# Sheet6_MCU_Antenna_Radio_Interface.net
KiCad netlist of a schematic drawn in Altium Designer
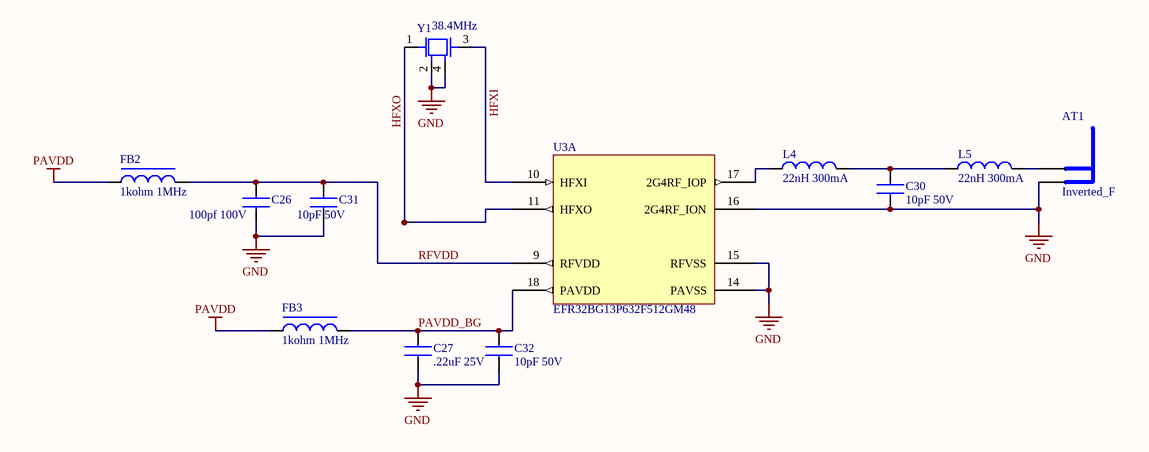
[diagram p0: Sheet6_MCU_Antenna_Radio_Interface.SchDoc]

(export (version "E")
  (design (tool "Eeschema 10.0.6"))
  (components
    (comp (ref "AT1")
      (value "Inverted_F")
      (footprint "F_ANTENNA")
      (description "Inverted-F Antenna for .062\" FR4")
      (libsource (lib "Schlib1 (1)") (part "INVERTED-F_ANTENNA"))
    )
    (comp (ref "C26")
      (value "100pf 100V")
      (footprint "CAP_0805_1_4MM")
      (description "Capacitor 100 pF 100 VDC PU=4000 ST, CL21C101JCANNNC, Samsung")
      (fields
        (field (name "MANUFACTURER") "Samsung")
        (field (name "MANUFACTURER PART NUMBER") "CL21C101JCANNNC")
      )
      (libsource (lib "LPEDT_Parts") (part "CL21C101JCANNNC"))
    )
    (comp (ref "C27")
      (value ".22uF 25V")
      (footprint "CAP_0603_1MM")
      (fields
        (field (name "MANUFACTURER") "Taiyo Yuden")
        (field (name "MANUFACTURER PART NUMBER") "TMK107B7224KA-T")
        (field (name "TOLERANCE") "10%")
      )
      (libsource (lib "LPEDT_Parts") (part "TMK107B7224KA-T"))
    )
    (comp (ref "C30")
      (value "10pF 50V")
      (footprint "CAPC1005X06N")
      (description "Cap Ceramic 10pF 50V X7R 10% SMD 0402 125°C Paper T/R")
      (fields
        (field (name "MANUFACTURER") "KEMET")
        (field (name "MANUFACTURER PART NUMBER") "C0402C100K5RAC7867")
      )
      (libsource (lib "LPEDT_Parts") (part "C0402C100K5RAC7867"))
    )
    (comp (ref "C31")
      (value "10pF 50V")
      (footprint "CAP_0805_1_4MM")
      (description "Cap Ceramic 10pF 50V X7R 10% SMD 0402 125°C Paper T/R")
      (fields
        (field (name "MANUFACTURER") "KEMET")
        (field (name "MANUFACTURER PART NUMBER") "C0402C100K5RAC7867")
      )
      (libsource (lib "LPEDT_Parts") (part "C0402C100K5RAC7867"))
    )
    (comp (ref "C32")
      (value "10pF 50V")
      (footprint "CAP_0805_1_4MM")
      (description "Cap Ceramic 10pF 50V X7R 10% SMD 0402 125°C Paper T/R")
      (fields
        (field (name "MANUFACTURER") "KEMET")
        (field (name "MANUFACTURER PART NUMBER") "C0402C100K5RAC7867")
      )
      (libsource (lib "LPEDT_Parts") (part "C0402C100K5RAC7867"))
    )
    (comp (ref "FB2")
      (value "1kohm 1MHz")
      (footprint "CAP_0603_1MM")
      (fields
        (field (name "MANUFACTURER") "Wurth Electronics")
        (field (name "MANUFACTURER PART NUMBER") "74279266")
        (field (name "TOLERANCE") "25%")
      )
      (libsource (lib "LPEDT_Parts") (part "74279266"))
    )
    (comp (ref "FB3")
      (value "1kohm 1MHz")
      (footprint "CAP_0603_1MM")
      (fields
        (field (name "MANUFACTURER") "Wurth Electronics")
        (field (name "MANUFACTURER PART NUMBER") "74279266")
        (field (name "TOLERANCE") "25%")
      )
      (libsource (lib "LPEDT_Parts") (part "74279266"))
    )
    (comp (ref "L4")
      (value "22nH 300mA")
      (footprint "INDC1005X06N")
      (description "Fixed Inductors 22nH 5% Hi-Freq")
      (fields
        (field (name "MANUFACTURER") "Murata")
        (field (name "MANUFACTURER PART NUMBER") "LQG15HS22NJ02D")
      )
      (libsource (lib "LPEDT_Parts") (part "LQG15HS22NJ02D"))
    )
    (comp (ref "L5")
      (value "22nH 300mA")
      (footprint "INDC1005X06N")
      (description "Fixed Inductors 22nH 5% Hi-Freq")
      (fields
        (field (name "MANUFACTURER") "Murata")
        (field (name "MANUFACTURER PART NUMBER") "LQG15HS22NJ02D")
      )
      (libsource (lib "LPEDT_Parts") (part "LQG15HS22NJ02D"))
    )
    (comp (ref "U3")
      (value "EFR32BG13P632F512GM48")
      (footprint "QFN50P700X700X90_HS-49N")
      (description "BLUE PREMIUM QFN48 2.4G 19 DBM B")
      (fields
        (field (name "MANUFACTURER") "Silicon Labs")
        (field (name "MANUFACTURER PART NUMBER") "EFR32BG13P732F512GM48-B")
      )
      (libsource (lib "LPEDT_Parts") (part "EFR32BG13P732F512GM48-B_1"))
    )
    (comp (ref "Y1")
      (value "38.4MHz")
      (footprint "DFN130P200X45-4N")
      (fields (field (name "MANUFACTURER") "TXC") (field (name "MANUFACTURER PART NUMBER") "8Y38472012"))
      (libsource (lib "LPEDT_Parts") (part "8Y38472012"))
    )
  )
  (nets
    (net (code "1") (name "/HFXI") (class "Default")
      (node (ref "U3") (pin "10") (pinfunction "HFXI_10") (pintype "input"))
      (node (ref "Y1") (pin "3") (pinfunction "3_3") (pintype "passive"))
    )
    (net (code "2") (name "/HFXO") (class "Default")
      (node (ref "U3") (pin "11") (pinfunction "HFXO_11") (pintype "output"))
      (node (ref "Y1") (pin "1") (pinfunction "1_1") (pintype "passive"))
    )
    (net (code "3") (name "/PAVDD_BG") (class "Default")
      (node (ref "C27") (pin "1") (pinfunction "1_1") (pintype "passive"))
      (node (ref "C32") (pin "1") (pinfunction "1_1") (pintype "passive"))
      (node (ref "FB3") (pin "2") (pinfunction "2_2") (pintype "passive"))
      (node (ref "U3") (pin "18") (pinfunction "PAVDD_18") (pintype "output"))
    )
    (net (code "4") (name "/RFVDD") (class "Default")
      (node (ref "C26") (pin "1") (pinfunction "1_1") (pintype "passive"))
      (node (ref "C31") (pin "1") (pinfunction "1_1") (pintype "passive"))
      (node (ref "FB2") (pin "2") (pinfunction "2_2") (pintype "passive"))
      (node (ref "U3") (pin "9") (pinfunction "RFVDD_9") (pintype "output"))
    )
    (net (code "5") (name "GND") (class "Default")
      (node (ref "AT1") (pin "GND") (pinfunction "GND_GND") (pintype "passive"))
      (node (ref "C26") (pin "2") (pinfunction "2_2") (pintype "passive"))
      (node (ref "C27") (pin "2") (pinfunction "2_2") (pintype "passive"))
      (node (ref "C30") (pin "2") (pinfunction "2_2") (pintype "passive"))
      (node (ref "C31") (pin "2") (pinfunction "2_2") (pintype "passive"))
      (node (ref "C32") (pin "2") (pinfunction "2_2") (pintype "passive"))
      (node (ref "U3") (pin "14") (pinfunction "PAVSS_14") (pintype "power_in"))
      (node (ref "U3") (pin "15") (pinfunction "RFVSS_15") (pintype "power_in"))
      (node (ref "U3") (pin "16") (pinfunction "2G4RF_ION_16") (pintype "power_in"))
      (node (ref "Y1") (pin "2") (pinfunction "2_2") (pintype "passive"))
      (node (ref "Y1") (pin "4") (pinfunction "4_4") (pintype "passive"))
    )
    (net (code "6") (name "Net-(AT1-PadFEED)") (class "Default")
      (node (ref "AT1") (pin "FEED") (pinfunction "FEED_FEED") (pintype "passive"))
      (node (ref "L5") (pin "2") (pinfunction "2_2") (pintype "passive"))
    )
    (net (code "7") (name "Net-(C30-Pad1)") (class "Default")
      (node (ref "C30") (pin "1") (pinfunction "1_1") (pintype "passive"))
      (node (ref "L4") (pin "2") (pinfunction "2_2") (pintype "passive"))
      (node (ref "L5") (pin "1") (pinfunction "1_1") (pintype "passive"))
    )
    (net (code "8") (name "Net-(U3A-2G4RF_IOP)") (class "Default")
      (node (ref "L4") (pin "1") (pinfunction "1_1") (pintype "passive"))
      (node (ref "U3") (pin "17") (pinfunction "2G4RF_IOP_17") (pintype "output"))
    )
    (net (code "9") (name "PAVDD") (class "Default")
      (node (ref "FB2") (pin "1") (pinfunction "1_1") (pintype "passive"))
      (node (ref "FB3") (pin "1") (pinfunction "1_1") (pintype "passive"))
    )
  )
)
